# line_kick.net
KiCad netlist of a schematic drawn in EAGLE
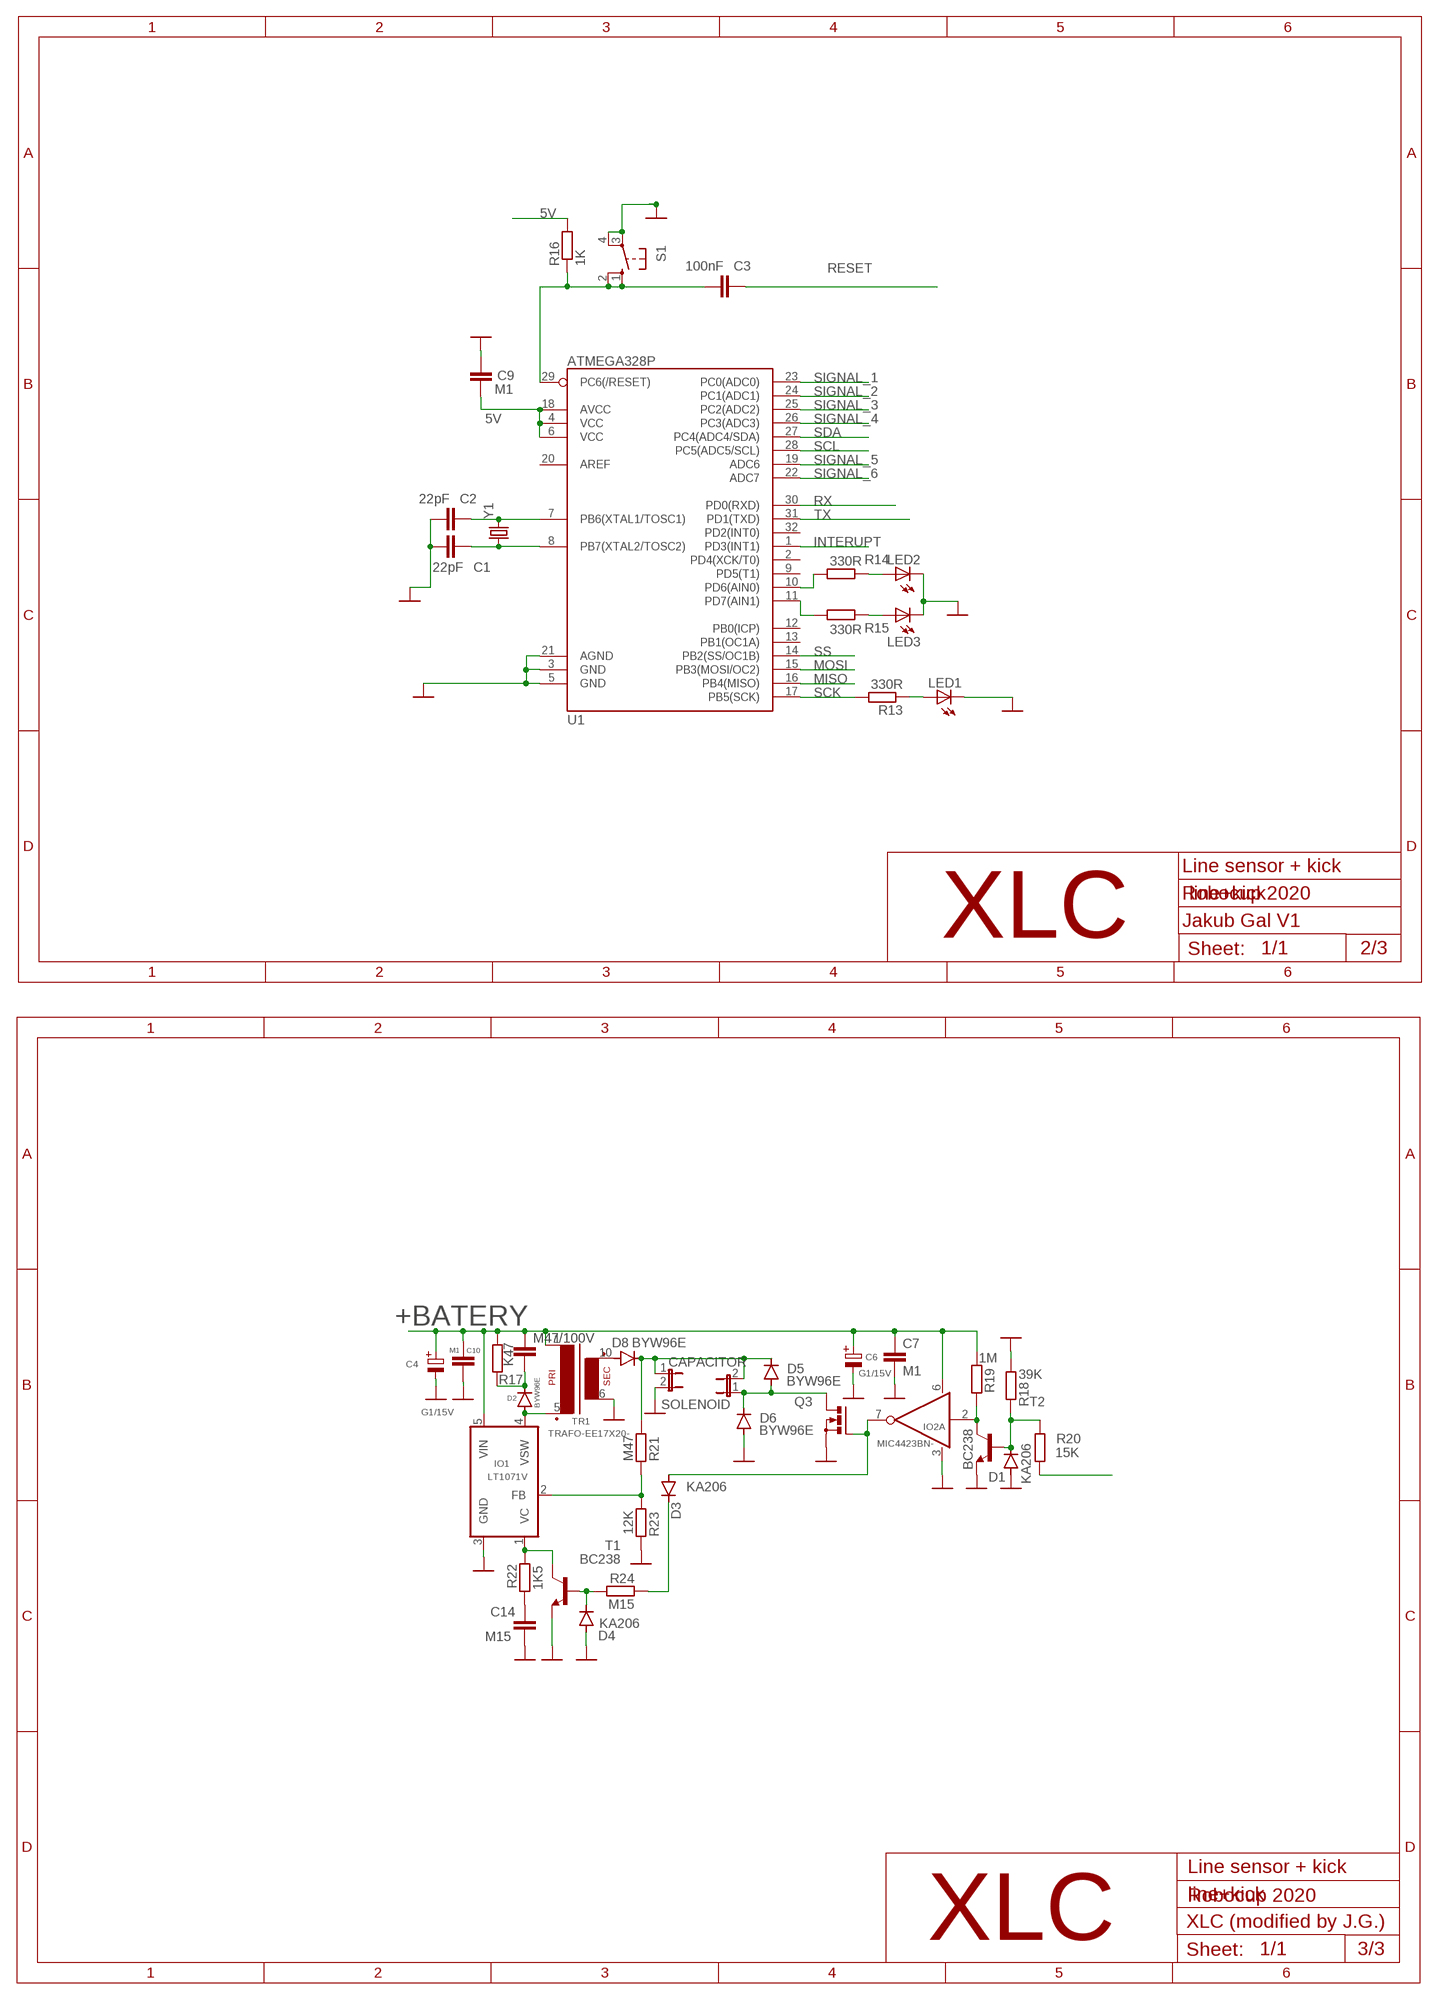
[diagram p0: schematic, sheet 1, part 1 of 2]
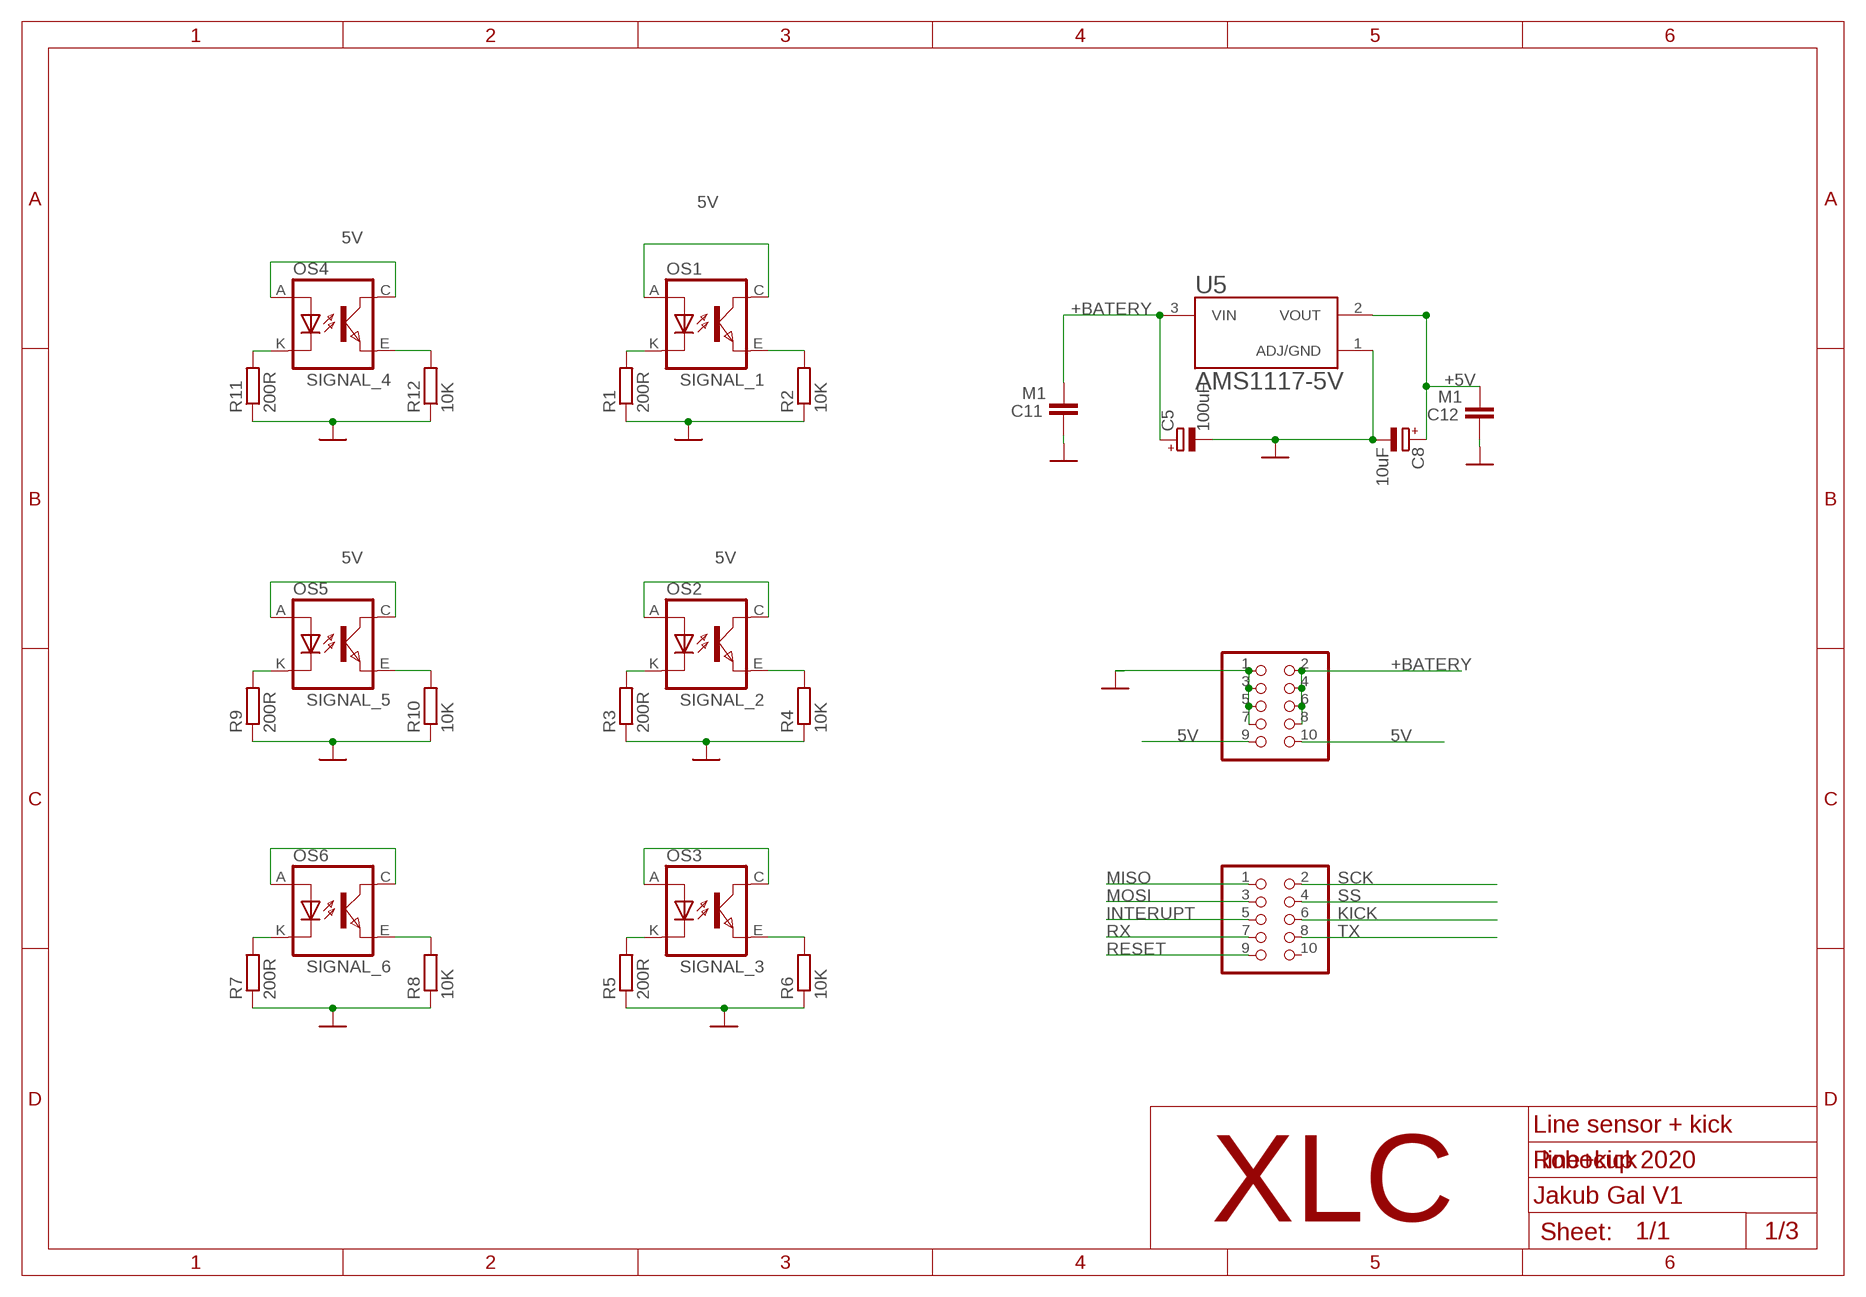
[diagram p1: schematic, sheet 1, part 2 of 2]

(export (version "E")
  (design (tool "Eeschema 10.0.6"))
  (components
    (comp (ref "C1")
      (value "22pF")
      (footprint "eagle-import:C0603")
      (libsource (lib "eagle-import") (part "C-EUC0603"))
    )
    (comp (ref "C2")
      (value "22pF")
      (footprint "eagle-import:C0603")
      (libsource (lib "eagle-import") (part "C-EUC0603"))
    )
    (comp (ref "C3")
      (value "100nF")
      (footprint "eagle-import:C0603")
      (libsource (lib "eagle-import") (part "C-EUC0603"))
    )
    (comp (ref "C4")
      (value "G1/15V")
      (footprint "eagle-import:E-2,5_7-RAD")
      (libsource (lib "eagle-import") (part "KOND-ELEKT-2,5/7"))
    )
    (comp (ref "C5")
      (value "100uF")
      (footprint "eagle-import:UD-6,3X7,7_NICHICON")
      (libsource (lib "eagle-import") (part "CPOL-EUUD-6,3X7,7"))
    )
    (comp (ref "C6")
      (value "G1/15V")
      (footprint "eagle-import:E-2,5_7-RAD")
      (libsource (lib "eagle-import") (part "KOND-ELEKT-2,5/7"))
    )
    (comp (ref "C7")
      (value "M1")
      (footprint "eagle-import:C0805K")
      (libsource (lib "eagle-import") (part "resistor_348_C-EUC0805K"))
    )
    (comp (ref "C8")
      (value "10uF")
      (footprint "eagle-import:UD-4X5,8_NICHICON")
      (libsource (lib "eagle-import") (part "CPOL-EUUD-4X5,8"))
    )
    (comp (ref "C9")
      (value "M1")
      (footprint "eagle-import:C0603")
      (libsource (lib "eagle-import") (part "C-EUC0603"))
    )
    (comp (ref "C10")
      (value "M1")
      (footprint "eagle-import:C0805K")
      (libsource (lib "eagle-import") (part "resistor_348_C-EUC0805K"))
    )
    (comp (ref "C11")
      (value "M1")
      (footprint "eagle-import:C0603")
      (libsource (lib "eagle-import") (part "C-EUC0603"))
    )
    (comp (ref "C12")
      (value "M1")
      (footprint "eagle-import:C0603")
      (libsource (lib "eagle-import") (part "C-EUC0603"))
    )
    (comp (ref "C14")
      (value "M15")
      (footprint "eagle-import:C0805K")
      (libsource (lib "eagle-import") (part "resistor_348_C-EUC0805K"))
    )
    (comp (ref "CAPACITOR")
      (value "JP1E")
      (footprint "eagle-import:JP1")
      (libsource (lib "eagle-import") (part "JP1E"))
    )
    (comp (ref "D1")
      (value "KA206")
      (footprint "eagle-import:D-7.5")
      (libsource (lib "eagle-import") (part "DIODE-D-7.5"))
    )
    (comp (ref "D2")
      (value "BYW96E")
      (footprint "eagle-import:SOD64-10")
      (libsource (lib "eagle-import") (part "BYW96"))
    )
    (comp (ref "D3")
      (value "KA206")
      (footprint "eagle-import:D-7.5")
      (libsource (lib "eagle-import") (part "DIODE-D-7.5"))
    )
    (comp (ref "D4")
      (value "KA206")
      (footprint "eagle-import:D-7.5")
      (libsource (lib "eagle-import") (part "DIODE-D-7.5"))
    )
    (comp (ref "D5")
      (value "BYW96E")
      (footprint "eagle-import:SOD64-10")
      (libsource (lib "eagle-import") (part "BYW96"))
    )
    (comp (ref "D6")
      (value "BYW96E")
      (footprint "eagle-import:SOD64-10")
      (libsource (lib "eagle-import") (part "BYW96"))
    )
    (comp (ref "D8")
      (value "BYW96E")
      (footprint "eagle-import:SOD64-10")
      (libsource (lib "eagle-import") (part "BYW96"))
    )
    (comp (ref "IO1")
      (value "LT1071V")
      (footprint "eagle-import:TO-220-5P")
      (libsource (lib "eagle-import") (part "LT1071V"))
    )
    (comp (ref "IO2")
      (value "MIC4423BN-")
      (footprint "eagle-import:DIL8")
      (libsource (lib "eagle-import") (part "MIC4423BN-"))
    )
    (comp (ref "JP2")
      (value "PINHD-2X5")
      (footprint "eagle-import:2X05")
      (libsource (lib "eagle-import") (part "PINHD-2X5"))
    )
    (comp (ref "JP3")
      (value "PINHD-2X5")
      (footprint "eagle-import:2X05")
      (libsource (lib "eagle-import") (part "PINHD-2X5"))
    )
    (comp (ref "LED1")
      (value "LEDCHIPLED_0603")
      (footprint "eagle-import:CHIPLED_0603")
      (libsource (lib "eagle-import") (part "LEDCHIPLED_0603"))
    )
    (comp (ref "LED2")
      (value "LEDCHIPLED_0603")
      (footprint "eagle-import:CHIPLED_0603")
      (libsource (lib "eagle-import") (part "LEDCHIPLED_0603"))
    )
    (comp (ref "LED3")
      (value "LEDCHIPLED_0603")
      (footprint "eagle-import:CHIPLED_0603")
      (libsource (lib "eagle-import") (part "LEDCHIPLED_0603"))
    )
    (comp (ref "M47/100V")
      (value "C-EUC0805K")
      (footprint "eagle-import:C0805K")
      (libsource (lib "eagle-import") (part "resistor_348_C-EUC0805K"))
    )
    (comp (ref "OS1")
      (value "TCRT5000")
      (footprint "eagle-import:TCRT5000")
      (libsource (lib "eagle-import") (part "TCRT5000"))
    )
    (comp (ref "OS2")
      (value "TCRT5000")
      (footprint "eagle-import:TCRT5000")
      (libsource (lib "eagle-import") (part "TCRT5000"))
    )
    (comp (ref "OS3")
      (value "TCRT5000")
      (footprint "eagle-import:TCRT5000")
      (libsource (lib "eagle-import") (part "TCRT5000"))
    )
    (comp (ref "OS4")
      (value "TCRT5000")
      (footprint "eagle-import:TCRT5000")
      (fields (field (name "SPICEPREFIX") "O"))
      (libsource (lib "eagle-import") (part "TCRT5000"))
    )
    (comp (ref "OS5")
      (value "TCRT5000")
      (footprint "eagle-import:TCRT5000")
      (libsource (lib "eagle-import") (part "TCRT5000"))
    )
    (comp (ref "OS6")
      (value "TCRT5000")
      (footprint "eagle-import:TCRT5000")
      (fields (field (name "SPICEPREFIX") "O"))
      (libsource (lib "eagle-import") (part "TCRT5000"))
    )
    (comp (ref "Q3")
      (value "PMOSFET_NTO220BV")
      (footprint "eagle-import:TO220BV")
      (libsource (lib "eagle-import") (part "PMOSFET_NTO220BV"))
    )
    (comp (ref "R1")
      (value "200R")
      (footprint "eagle-import:R0603")
      (libsource (lib "eagle-import") (part "R-EU_R0603"))
    )
    (comp (ref "R2")
      (value "10K")
      (footprint "eagle-import:R0603")
      (libsource (lib "eagle-import") (part "R-EU_R0603"))
    )
    (comp (ref "R3")
      (value "200R")
      (footprint "eagle-import:R0603")
      (libsource (lib "eagle-import") (part "R-EU_R0603"))
    )
    (comp (ref "R4")
      (value "10K")
      (footprint "eagle-import:R0603")
      (libsource (lib "eagle-import") (part "R-EU_R0603"))
    )
    (comp (ref "R5")
      (value "200R")
      (footprint "eagle-import:R0603")
      (libsource (lib "eagle-import") (part "R-EU_R0603"))
    )
    (comp (ref "R6")
      (value "10K")
      (footprint "eagle-import:R0603")
      (libsource (lib "eagle-import") (part "R-EU_R0603"))
    )
    (comp (ref "R7")
      (value "200R")
      (footprint "eagle-import:R0603")
      (libsource (lib "eagle-import") (part "R-EU_R0603"))
    )
    (comp (ref "R8")
      (value "10K")
      (footprint "eagle-import:R0603")
      (libsource (lib "eagle-import") (part "R-EU_R0603"))
    )
    (comp (ref "R9")
      (value "200R")
      (footprint "eagle-import:R0603")
      (libsource (lib "eagle-import") (part "R-EU_R0603"))
    )
    (comp (ref "R10")
      (value "10K")
      (footprint "eagle-import:R0603")
      (libsource (lib "eagle-import") (part "R-EU_R0603"))
    )
    (comp (ref "R11")
      (value "200R")
      (footprint "eagle-import:R0603")
      (libsource (lib "eagle-import") (part "R-EU_R0603"))
    )
    (comp (ref "R12")
      (value "10K")
      (footprint "eagle-import:R0603")
      (libsource (lib "eagle-import") (part "R-EU_R0603"))
    )
    (comp (ref "R13")
      (value "330R")
      (footprint "eagle-import:R0603")
      (libsource (lib "eagle-import") (part "R-EU_R0603"))
    )
    (comp (ref "R14")
      (value "330R")
      (footprint "eagle-import:R0603")
      (libsource (lib "eagle-import") (part "R-EU_R0603"))
    )
    (comp (ref "R15")
      (value "330R")
      (footprint "eagle-import:R0603")
      (libsource (lib "eagle-import") (part "R-EU_R0603"))
    )
    (comp (ref "R16")
      (value "1K")
      (footprint "eagle-import:R0603")
      (libsource (lib "eagle-import") (part "R-EU_R0603"))
    )
    (comp (ref "R17")
      (value "K47")
      (footprint "eagle-import:R0603")
      (libsource (lib "eagle-import") (part "resistor_348_R-EU_R0603"))
    )
    (comp (ref "R18")
      (value "39K")
      (footprint "eagle-import:R0603")
      (libsource (lib "eagle-import") (part "resistor_348_R-EU_R0603"))
    )
    (comp (ref "R19")
      (value "1M")
      (footprint "eagle-import:R0603")
      (libsource (lib "eagle-import") (part "resistor_348_R-EU_R0603"))
    )
    (comp (ref "R20")
      (value "15K")
      (footprint "eagle-import:R0603")
      (libsource (lib "eagle-import") (part "resistor_348_R-EU_R0603"))
    )
    (comp (ref "R21")
      (value "M47")
      (footprint "eagle-import:R0603")
      (libsource (lib "eagle-import") (part "resistor_348_R-EU_R0603"))
    )
    (comp (ref "R22")
      (value "1K5")
      (footprint "eagle-import:R0603")
      (libsource (lib "eagle-import") (part "resistor_348_R-EU_R0603"))
    )
    (comp (ref "R23")
      (value "12K")
      (footprint "eagle-import:R0603")
      (libsource (lib "eagle-import") (part "resistor_348_R-EU_R0603"))
    )
    (comp (ref "R24")
      (value "M15")
      (footprint "eagle-import:R0603")
      (libsource (lib "eagle-import") (part "resistor_348_R-EU_R0603"))
    )
    (comp (ref "S1")
      (value "10-XX")
      (footprint "eagle-import:B3F-10XX")
      (fields (field (name "MPN") "B3F-1000"))
      (libsource (lib "eagle-import") (part "10-XX"))
    )
    (comp (ref "SOLENOID")
      (value "JP1E")
      (footprint "eagle-import:JP1")
      (libsource (lib "eagle-import") (part "JP1E"))
    )
    (comp (ref "T1")
      (value "BC238")
      (footprint "eagle-import:TO92")
      (libsource (lib "eagle-import") (part "BC238"))
    )
    (comp (ref "T2")
      (value "BC238")
      (footprint "eagle-import:TO92")
      (libsource (lib "eagle-import") (part "BC238"))
    )
    (comp (ref "TR1")
      (value "TRAFO-EE17X20-")
      (footprint "eagle-import:TRAFO-EE17X20")
      (libsource (lib "eagle-import") (part "TRAFO-EE17X20-"))
    )
    (comp (ref "U1")
      (value "ATMEGA328P")
      (footprint "eagle-import:TQFP32-08")
      (libsource (lib "eagle-import") (part "ATMEGA328_SMT"))
    )
    (comp (ref "U5")
      (value "AMS1117-5V")
      (footprint "eagle-import:SOT229P700X180-4N")
      (fields (field (name "MF") "Advanced Monolithic Systems") (field (name "MP") "AMS1117-3.3"))
      (libsource (lib "eagle-import") (part "AMS1117-3.3"))
    )
    (comp (ref "Y1")
      (value "CRYSTALHC49US")
      (footprint "eagle-import:HC49US")
      (libsource (lib "eagle-import") (part "CRYSTALHC49US"))
    )
  )
  (nets
    (net (code "1") (name "/+5V") (class "Default")
      (node (ref "C12") (pin "1") (pinfunction "1_1") (pintype "passive"))
      (node (ref "C8") (pin "+") (pinfunction "+_+") (pintype "passive"))
      (node (ref "U5") (pin "2") (pinfunction "VOUT_2") (pintype "output"))
    )
    (net (code "2") (name "/+BATERY") (class "Default")
      (node (ref "C10") (pin "1") (pinfunction "1_1") (pintype "passive"))
      (node (ref "C11") (pin "1") (pinfunction "1_1") (pintype "passive"))
      (node (ref "C4") (pin "+") (pinfunction "+_+") (pintype "passive"))
      (node (ref "C5") (pin "+") (pinfunction "+_+") (pintype "passive"))
      (node (ref "C6") (pin "+") (pinfunction "+_+") (pintype "passive"))
      (node (ref "C7") (pin "1") (pinfunction "1_1") (pintype "passive"))
      (node (ref "IO1") (pin "5") (pinfunction "VIN_5") (pintype "power_in"))
      (node (ref "IO2") (pin "6") (pinfunction "VCC_6") (pintype "power_in"))
      (node (ref "JP3") (pin "2") (pinfunction "2_2") (pintype "passive"))
      (node (ref "JP3") (pin "4") (pinfunction "4_4") (pintype "passive"))
      (node (ref "JP3") (pin "6") (pinfunction "6_6") (pintype "passive"))
      (node (ref "JP3") (pin "8") (pinfunction "8_8") (pintype "passive"))
      (node (ref "M47/100V") (pin "1") (pinfunction "1_1") (pintype "passive"))
      (node (ref "R17") (pin "1") (pinfunction "1_1") (pintype "passive"))
      (node (ref "R19") (pin "2") (pinfunction "2_2") (pintype "passive"))
      (node (ref "TR1") (pin "1") (pinfunction "1_1") (pintype "passive"))
      (node (ref "U5") (pin "3") (pinfunction "VIN_3") (pintype "input"))
    )
    (net (code "3") (name "/5V") (class "Default")
      (node (ref "C9") (pin "1") (pinfunction "1_1") (pintype "passive"))
      (node (ref "JP3") (pin "10") (pinfunction "10_10") (pintype "passive"))
      (node (ref "JP3") (pin "9") (pinfunction "9_9") (pintype "passive"))
      (node (ref "OS1") (pin "A") (pinfunction "ANODE_A") (pintype "passive"))
      (node (ref "OS1") (pin "C") (pinfunction "COLLECTOR_C") (pintype "passive"))
      (node (ref "OS2") (pin "A") (pinfunction "ANODE_A") (pintype "passive"))
      (node (ref "OS2") (pin "C") (pinfunction "COLLECTOR_C") (pintype "passive"))
      (node (ref "OS3") (pin "A") (pinfunction "ANODE_A") (pintype "passive"))
      (node (ref "OS3") (pin "C") (pinfunction "COLLECTOR_C") (pintype "passive"))
      (node (ref "OS4") (pin "A") (pinfunction "ANODE_A") (pintype "passive"))
      (node (ref "OS4") (pin "C") (pinfunction "COLLECTOR_C") (pintype "passive"))
      (node (ref "OS5") (pin "A") (pinfunction "ANODE_A") (pintype "passive"))
      (node (ref "OS5") (pin "C") (pinfunction "COLLECTOR_C") (pintype "passive"))
      (node (ref "OS6") (pin "A") (pinfunction "ANODE_A") (pintype "passive"))
      (node (ref "OS6") (pin "C") (pinfunction "COLLECTOR_C") (pintype "passive"))
      (node (ref "R16") (pin "2") (pinfunction "2_2") (pintype "passive"))
      (node (ref "U1") (pin "18") (pinfunction "AVCC_18") (pintype "bidirectional"))
      (node (ref "U1") (pin "4") (pinfunction "VCC_4") (pintype "bidirectional"))
      (node (ref "U1") (pin "6") (pinfunction "VCC_6") (pintype "bidirectional"))
    )
    (net (code "4") (name "/INTERUPT") (class "Default")
      (node (ref "JP2") (pin "5") (pinfunction "5_5") (pintype "passive"))
      (node (ref "U1") (pin "1") (pinfunction "PD3(INT1)_1") (pintype "bidirectional"))
    )
    (net (code "5") (name "/KICK") (class "Default")
      (node (ref "JP2") (pin "6") (pinfunction "6_6") (pintype "passive"))
      (node (ref "R20") (pin "1") (pinfunction "1_1") (pintype "passive"))
    )
    (net (code "6") (name "/MISO") (class "Default")
      (node (ref "JP2") (pin "1") (pinfunction "1_1") (pintype "passive"))
      (node (ref "U1") (pin "16") (pinfunction "PB4(MISO)_16") (pintype "bidirectional"))
    )
    (net (code "7") (name "/MOSI") (class "Default")
      (node (ref "JP2") (pin "3") (pinfunction "3_3") (pintype "passive"))
      (node (ref "U1") (pin "15") (pinfunction "PB3(MOSI/OC2)_15") (pintype "bidirectional"))
    )
    (net (code "8") (name "/RESET") (class "Default")
      (node (ref "C3") (pin "2") (pinfunction "2_2") (pintype "passive"))
      (node (ref "JP2") (pin "9") (pinfunction "9_9") (pintype "passive"))
    )
    (net (code "9") (name "/RX") (class "Default")
      (node (ref "JP2") (pin "7") (pinfunction "7_7") (pintype "passive"))
      (node (ref "U1") (pin "30") (pinfunction "PD0(RXD)_30") (pintype "bidirectional"))
    )
    (net (code "10") (name "/SCK") (class "Default")
      (node (ref "JP2") (pin "2") (pinfunction "2_2") (pintype "passive"))
      (node (ref "R13") (pin "2") (pinfunction "2_2") (pintype "passive"))
      (node (ref "U1") (pin "17") (pinfunction "PB5(SCK)_17") (pintype "bidirectional"))
    )
    (net (code "11") (name "/SCL") (class "Default")
      (node (ref "U1") (pin "28") (pinfunction "PC5(ADC5/SCL)_28") (pintype "bidirectional"))
    )
    (net (code "12") (name "/SDA") (class "Default")
      (node (ref "U1") (pin "27") (pinfunction "PC4(ADC4/SDA)_27") (pintype "bidirectional"))
    )
    (net (code "13") (name "/SIGNAL_1") (class "Default")
      (node (ref "OS1") (pin "E") (pinfunction "EMITTER_E") (pintype "passive"))
      (node (ref "R2") (pin "2") (pinfunction "2_2") (pintype "passive"))
      (node (ref "U1") (pin "23") (pinfunction "PC0(ADC0)_23") (pintype "bidirectional"))
    )
    (net (code "14") (name "/SIGNAL_2") (class "Default")
      (node (ref "OS2") (pin "E") (pinfunction "EMITTER_E") (pintype "passive"))
      (node (ref "R4") (pin "2") (pinfunction "2_2") (pintype "passive"))
      (node (ref "U1") (pin "24") (pinfunction "PC1(ADC1)_24") (pintype "bidirectional"))
    )
    (net (code "15") (name "/SIGNAL_3") (class "Default")
      (node (ref "OS3") (pin "E") (pinfunction "EMITTER_E") (pintype "passive"))
      (node (ref "R6") (pin "2") (pinfunction "2_2") (pintype "passive"))
      (node (ref "U1") (pin "25") (pinfunction "PC2(ADC2)_25") (pintype "bidirectional"))
    )
    (net (code "16") (name "/SIGNAL_4") (class "Default")
      (node (ref "OS4") (pin "E") (pinfunction "EMITTER_E") (pintype "passive"))
      (node (ref "R12") (pin "2") (pinfunction "2_2") (pintype "passive"))
      (node (ref "U1") (pin "26") (pinfunction "PC3(ADC3)_26") (pintype "bidirectional"))
    )
    (net (code "17") (name "/SIGNAL_5") (class "Default")
      (node (ref "OS5") (pin "E") (pinfunction "EMITTER_E") (pintype "passive"))
      (node (ref "R10") (pin "2") (pinfunction "2_2") (pintype "passive"))
      (node (ref "U1") (pin "19") (pinfunction "ADC6_19") (pintype "bidirectional"))
    )
    (net (code "18") (name "/SIGNAL_6") (class "Default")
      (node (ref "OS6") (pin "E") (pinfunction "EMITTER_E") (pintype "passive"))
      (node (ref "R8") (pin "2") (pinfunction "2_2") (pintype "passive"))
      (node (ref "U1") (pin "22") (pinfunction "ADC7_22") (pintype "bidirectional"))
    )
    (net (code "19") (name "/SS") (class "Default")
      (node (ref "JP2") (pin "4") (pinfunction "4_4") (pintype "passive"))
      (node (ref "U1") (pin "14") (pinfunction "PB2(SS/OC1B)_14") (pintype "bidirectional"))
    )
    (net (code "20") (name "/TX") (class "Default")
      (node (ref "JP2") (pin "8") (pinfunction "8_8") (pintype "passive"))
      (node (ref "U1") (pin "31") (pinfunction "PD1(TXD)_31") (pintype "bidirectional"))
    )
    (net (code "21") (name "GND") (class "Default")
      (node (ref "C1") (pin "1") (pinfunction "1_1") (pintype "passive"))
      (node (ref "C10") (pin "2") (pinfunction "2_2") (pintype "passive"))
      (node (ref "C11") (pin "2") (pinfunction "2_2") (pintype "passive"))
      (node (ref "C12") (pin "2") (pinfunction "2_2") (pintype "passive"))
      (node (ref "C14") (pin "2") (pinfunction "2_2") (pintype "passive"))
      (node (ref "C2") (pin "1") (pinfunction "1_1") (pintype "passive"))
      (node (ref "C4") (pin "-") (pinfunction "-_-") (pintype "passive"))
      (node (ref "C5") (pin "-") (pinfunction "-_-") (pintype "passive"))
      (node (ref "C6") (pin "-") (pinfunction "-_-") (pintype "passive"))
      (node (ref "C7") (pin "2") (pinfunction "2_2") (pintype "passive"))
      (node (ref "C8") (pin "-") (pinfunction "-_-") (pintype "passive"))
      (node (ref "C9") (pin "2") (pinfunction "2_2") (pintype "passive"))
      (node (ref "CAPACITOR") (pin "2") (pinfunction "2_2") (pintype "passive"))
      (node (ref "D1") (pin "A") (pinfunction "A_A") (pintype "passive"))
      (node (ref "D4") (pin "A") (pinfunction "A_A") (pintype "passive"))
      (node (ref "D6") (pin "A") (pinfunction "A_A") (pintype "passive"))
      (node (ref "IO1") (pin "3") (pinfunction "GND_3") (pintype "power_in"))
      (node (ref "IO2") (pin "3") (pinfunction "GND_3") (pintype "power_in"))
      (node (ref "JP3") (pin "1") (pinfunction "1_1") (pintype "passive"))
      (node (ref "JP3") (pin "3") (pinfunction "3_3") (pintype "passive"))
      (node (ref "JP3") (pin "5") (pinfunction "5_5") (pintype "passive"))
      (node (ref "JP3") (pin "7") (pinfunction "7_7") (pintype "passive"))
      (node (ref "LED1") (pin "C") (pinfunction "C_C") (pintype "passive"))
      (node (ref "LED2") (pin "C") (pinfunction "C_C") (pintype "passive"))
      (node (ref "LED3") (pin "C") (pinfunction "C_C") (pintype "passive"))
      (node (ref "Q3") (pin "S") (pinfunction "S_S") (pintype "passive"))
      (node (ref "R1") (pin "1") (pinfunction "1_1") (pintype "passive"))
      (node (ref "R10") (pin "1") (pinfunction "1_1") (pintype "passive"))
      (node (ref "R11") (pin "1") (pinfunction "1_1") (pintype "passive"))
      (node (ref "R12") (pin "1") (pinfunction "1_1") (pintype "passive"))
      (node (ref "R18") (pin "2") (pinfunction "2_2") (pintype "passive"))
      (node (ref "R2") (pin "1") (pinfunction "1_1") (pintype "passive"))
      (node (ref "R23") (pin "1") (pinfunction "1_1") (pintype "passive"))
      (node (ref "R3") (pin "1") (pinfunction "1_1") (pintype "passive"))
      (node (ref "R4") (pin "1") (pinfunction "1_1") (pintype "passive"))
      (node (ref "R5") (pin "1") (pinfunction "1_1") (pintype "passive"))
      (node (ref "R6") (pin "1") (pinfunction "1_1") (pintype "passive"))
      (node (ref "R7") (pin "1") (pinfunction "1_1") (pintype "passive"))
      (node (ref "R8") (pin "1") (pinfunction "1_1") (pintype "passive"))
      (node (ref "R9") (pin "1") (pinfunction "1_1") (pintype "passive"))
      (node (ref "S1") (pin "3") (pinfunction "P_3") (pintype "passive"))
      (node (ref "S1") (pin "4") (pinfunction "P1_4") (pintype "passive"))
      (node (ref "T1") (pin "1") (pinfunction "E_1") (pintype "passive"))
      (node (ref "T2") (pin "1") (pinfunction "E_1") (pintype "passive"))
      (node (ref "TR1") (pin "6") (pinfunction "3_6") (pintype "passive"))
      (node (ref "U1") (pin "21") (pinfunction "AGND_21") (pintype "bidirectional"))
      (node (ref "U1") (pin "3") (pinfunction "GND_3") (pintype "bidirectional"))
      (node (ref "U1") (pin "5") (pinfunction "GND_5") (pintype "bidirectional"))
      (node (ref "U5") (pin "1") (pinfunction "ADJ/GND_1") (pintype "power_in"))
    )
    (net (code "22") (name "Net-(C14-Pad1)") (class "Default")
      (node (ref "C14") (pin "1") (pinfunction "1_1") (pintype "passive"))
      (node (ref "R22") (pin "2") (pinfunction "2_2") (pintype "passive"))
    )
    (net (code "23") (name "Net-(CAPACITOR-Pad1)") (class "Default")
      (node (ref "CAPACITOR") (pin "1") (pinfunction "1_1") (pintype "passive"))
      (node (ref "D5") (pin "C") (pinfunction "C_C") (pintype "passive"))
      (node (ref "D8") (pin "C") (pinfunction "C_C") (pintype "passive"))
      (node (ref "R21") (pin "2") (pinfunction "2_2") (pintype "passive"))
      (node (ref "SOLENOID") (pin "2") (pinfunction "2_2") (pintype "passive"))
    )
    (net (code "24") (name "Net-(D2-PadC)") (class "Default")
      (node (ref "D2") (pin "C") (pinfunction "C_C") (pintype "passive"))
      (node (ref "M47/100V") (pin "2") (pinfunction "2_2") (pintype "passive"))
      (node (ref "R17") (pin "2") (pinfunction "2_2") (pintype "passive"))
    )
    (net (code "25") (name "Net-(D3-PadC)") (class "Default")
      (node (ref "D3") (pin "C") (pinfunction "C_C") (pintype "passive"))
      (node (ref "R24") (pin "1") (pinfunction "1_1") (pintype "passive"))
    )
    (net (code "26") (name "Net-(D5-PadA)") (class "Default")
      (node (ref "D5") (pin "A") (pinfunction "A_A") (pintype "passive"))
      (node (ref "D6") (pin "C") (pinfunction "C_C") (pintype "passive"))
      (node (ref "Q3") (pin "D") (pinfunction "D_D") (pintype "passive"))
      (node (ref "SOLENOID") (pin "1") (pinfunction "1_1") (pintype "passive"))
    )
    (net (code "27") (name "Net-(IO1-FB)") (class "Default")
      (node (ref "IO1") (pin "2") (pinfunction "FB_2") (pintype "input"))
      (node (ref "R21") (pin "1") (pinfunction "1_1") (pintype "passive"))
      (node (ref "R23") (pin "2") (pinfunction "2_2") (pintype "passive"))
    )
    (net (code "28") (name "Net-(IO1-VC)") (class "Default")
      (node (ref "IO1") (pin "1") (pinfunction "VC_1") (pintype "input"))
      (node (ref "R22") (pin "1") (pinfunction "1_1") (pintype "passive"))
      (node (ref "T1") (pin "3") (pinfunction "C_3") (pintype "passive"))
    )
    (net (code "29") (name "Net-(IO1-VSW)") (class "Default")
      (node (ref "D2") (pin "A") (pinfunction "A_A") (pintype "passive"))
      (node (ref "IO1") (pin "4") (pinfunction "VSW_4") (pintype "output"))
      (node (ref "TR1") (pin "5") (pinfunction "2_5") (pintype "passive"))
    )
    (net (code "30") (name "Net-(IO2A-I)") (class "Default")
      (node (ref "IO2") (pin "2") (pinfunction "I_2") (pintype "input"))
      (node (ref "R19") (pin "1") (pinfunction "1_1") (pintype "passive"))
      (node (ref "T2") (pin "3") (pinfunction "C_3") (pintype "passive"))
    )
    (net (code "31") (name "Net-(IO2A-O)") (class "Default")
      (node (ref "D3") (pin "A") (pinfunction "A_A") (pintype "passive"))
      (node (ref "IO2") (pin "7") (pinfunction "O_7") (pintype "output"))
      (node (ref "Q3") (pin "G") (pinfunction "G_G") (pintype "passive"))
    )
    (net (code "32") (name "Net-(LED1-PadA)") (class "Default")
      (node (ref "LED1") (pin "A") (pinfunction "A_A") (pintype "passive"))
      (node (ref "R13") (pin "1") (pinfunction "1_1") (pintype "passive"))
    )
    (net (code "33") (name "Net-(LED2-PadA)") (class "Default")
      (node (ref "LED2") (pin "A") (pinfunction "A_A") (pintype "passive"))
      (node (ref "R14") (pin "1") (pinfunction "1_1") (pintype "passive"))
    )
    (net (code "34") (name "Net-(LED3-PadA)") (class "Default")
      (node (ref "LED3") (pin "A") (pinfunction "A_A") (pintype "passive"))
      (node (ref "R15") (pin "1") (pinfunction "1_1") (pintype "passive"))
    )
    (net (code "35") (name "Net-(OS1-CATHODE)") (class "Default")
      (node (ref "OS1") (pin "K") (pinfunction "CATHODE_K") (pintype "passive"))
      (node (ref "R1") (pin "2") (pinfunction "2_2") (pintype "passive"))
    )
    (net (code "36") (name "Net-(OS2-CATHODE)") (class "Default")
      (node (ref "OS2") (pin "K") (pinfunction "CATHODE_K") (pintype "passive"))
      (node (ref "R3") (pin "2") (pinfunction "2_2") (pintype "passive"))
    )
    (net (code "37") (name "Net-(OS3-CATHODE)") (class "Default")
      (node (ref "OS3") (pin "K") (pinfunction "CATHODE_K") (pintype "passive"))
      (node (ref "R5") (pin "2") (pinfunction "2_2") (pintype "passive"))
    )
    (net (code "38") (name "Net-(OS4-CATHODE)") (class "Default")
      (node (ref "OS4") (pin "K") (pinfunction "CATHODE_K") (pintype "passive"))
      (node (ref "R11") (pin "2") (pinfunction "2_2") (pintype "passive"))
    )
    (net (code "39") (name "Net-(OS5-CATHODE)") (class "Default")
      (node (ref "OS5") (pin "K") (pinfunction "CATHODE_K") (pintype "passive"))
      (node (ref "R9") (pin "2") (pinfunction "2_2") (pintype "passive"))
    )
    (net (code "40") (name "Net-(OS6-CATHODE)") (class "Default")
      (node (ref "OS6") (pin "K") (pinfunction "CATHODE_K") (pintype "passive"))
      (node (ref "R7") (pin "2") (pinfunction "2_2") (pintype "passive"))
    )
    (net (code "41") (name "Net-(S1-S)") (class "Default")
      (node (ref "C3") (pin "1") (pinfunction "1_1") (pintype "passive"))
      (node (ref "R16") (pin "1") (pinfunction "1_1") (pintype "passive"))
      (node (ref "S1") (pin "1") (pinfunction "S_1") (pintype "passive"))
      (node (ref "S1") (pin "2") (pinfunction "S1_2") (pintype "passive"))
      (node (ref "U1") (pin "29") (pinfunction "PC6(/RESET)_29") (pintype "bidirectional"))
    )
    (net (code "42") (name "Net-(T1-B)") (class "Default")
      (node (ref "D4") (pin "C") (pinfunction "C_C") (pintype "passive"))
      (node (ref "R24") (pin "2") (pinfunction "2_2") (pintype "passive"))
      (node (ref "T1") (pin "2") (pinfunction "B_2") (pintype "passive"))
    )
    (net (code "43") (name "Net-(T2-B)") (class "Default")
      (node (ref "D1") (pin "C") (pinfunction "C_C") (pintype "passive"))
      (node (ref "R18") (pin "1") (pinfunction "1_1") (pintype "passive"))
      (node (ref "R20") (pin "2") (pinfunction "2_2") (pintype "passive"))
      (node (ref "T2") (pin "2") (pinfunction "B_2") (pintype "passive"))
    )
    (net (code "44") (name "Net-(TR1-4)") (class "Default")
      (node (ref "D8") (pin "A") (pinfunction "A_A") (pintype "passive"))
      (node (ref "TR1") (pin "10") (pinfunction "4_10") (pintype "passive"))
    )
    (net (code "45") (name "Net-(U1-PB6(XTAL1{slash}TOSC1))") (class "Default")
      (node (ref "C2") (pin "2") (pinfunction "2_2") (pintype "passive"))
      (node (ref "U1") (pin "7") (pinfunction "PB6(XTAL1/TOSC1)_7") (pintype "bidirectional"))
      (node (ref "Y1") (pin "2") (pinfunction "2_2") (pintype "passive"))
    )
    (net (code "46") (name "Net-(U1-PB7(XTAL2{slash}TOSC2))") (class "Default")
      (node (ref "C1") (pin "2") (pinfunction "2_2") (pintype "passive"))
      (node (ref "U1") (pin "8") (pinfunction "PB7(XTAL2/TOSC2)_8") (pintype "bidirectional"))
      (node (ref "Y1") (pin "1") (pinfunction "1_1") (pintype "passive"))
    )
    (net (code "47") (name "Net-(U1-PD6(AIN0))") (class "Default")
      (node (ref "R14") (pin "2") (pinfunction "2_2") (pintype "passive"))
      (node (ref "U1") (pin "10") (pinfunction "PD6(AIN0)_10") (pintype "bidirectional"))
    )
    (net (code "48") (name "Net-(U1-PD7(AIN1))") (class "Default")
      (node (ref "R15") (pin "2") (pinfunction "2_2") (pintype "passive"))
      (node (ref "U1") (pin "11") (pinfunction "PD7(AIN1)_11") (pintype "bidirectional"))
    )
    (net (code "49") (name "unconnected-(JP2-Pad10)") (class "Default")
      (node (ref "JP2") (pin "10") (pinfunction "10_10") (pintype "passive"))
    )
    (net (code "50") (name "unconnected-(U1-AREF-Pad20)") (class "Default")
      (node (ref "U1") (pin "20") (pinfunction "AREF_20") (pintype "bidirectional"))
    )
    (net (code "51") (name "unconnected-(U1-PB0(ICP)-Pad12)") (class "Default")
      (node (ref "U1") (pin "12") (pinfunction "PB0(ICP)_12") (pintype "bidirectional"))
    )
    (net (code "52") (name "unconnected-(U1-PB1(OC1A)-Pad13)") (class "Default")
      (node (ref "U1") (pin "13") (pinfunction "PB1(OC1A)_13") (pintype "bidirectional"))
    )
    (net (code "53") (name "unconnected-(U1-PD2(INT0)-Pad32)") (class "Default")
      (node (ref "U1") (pin "32") (pinfunction "PD2(INT0)_32") (pintype "bidirectional"))
    )
    (net (code "54") (name "unconnected-(U1-PD4(XCK{slash}T0)-Pad2)") (class "Default")
      (node (ref "U1") (pin "2") (pinfunction "PD4(XCK/T0)_2") (pintype "bidirectional"))
    )
    (net (code "55") (name "unconnected-(U1-PD5(T1)-Pad9)") (class "Default")
      (node (ref "U1") (pin "9") (pinfunction "PD5(T1)_9") (pintype "bidirectional"))
    )
  )
)
